# 0134-logic-level-shifter-x8.net
KiCad netlist of a schematic drawn in EAGLE
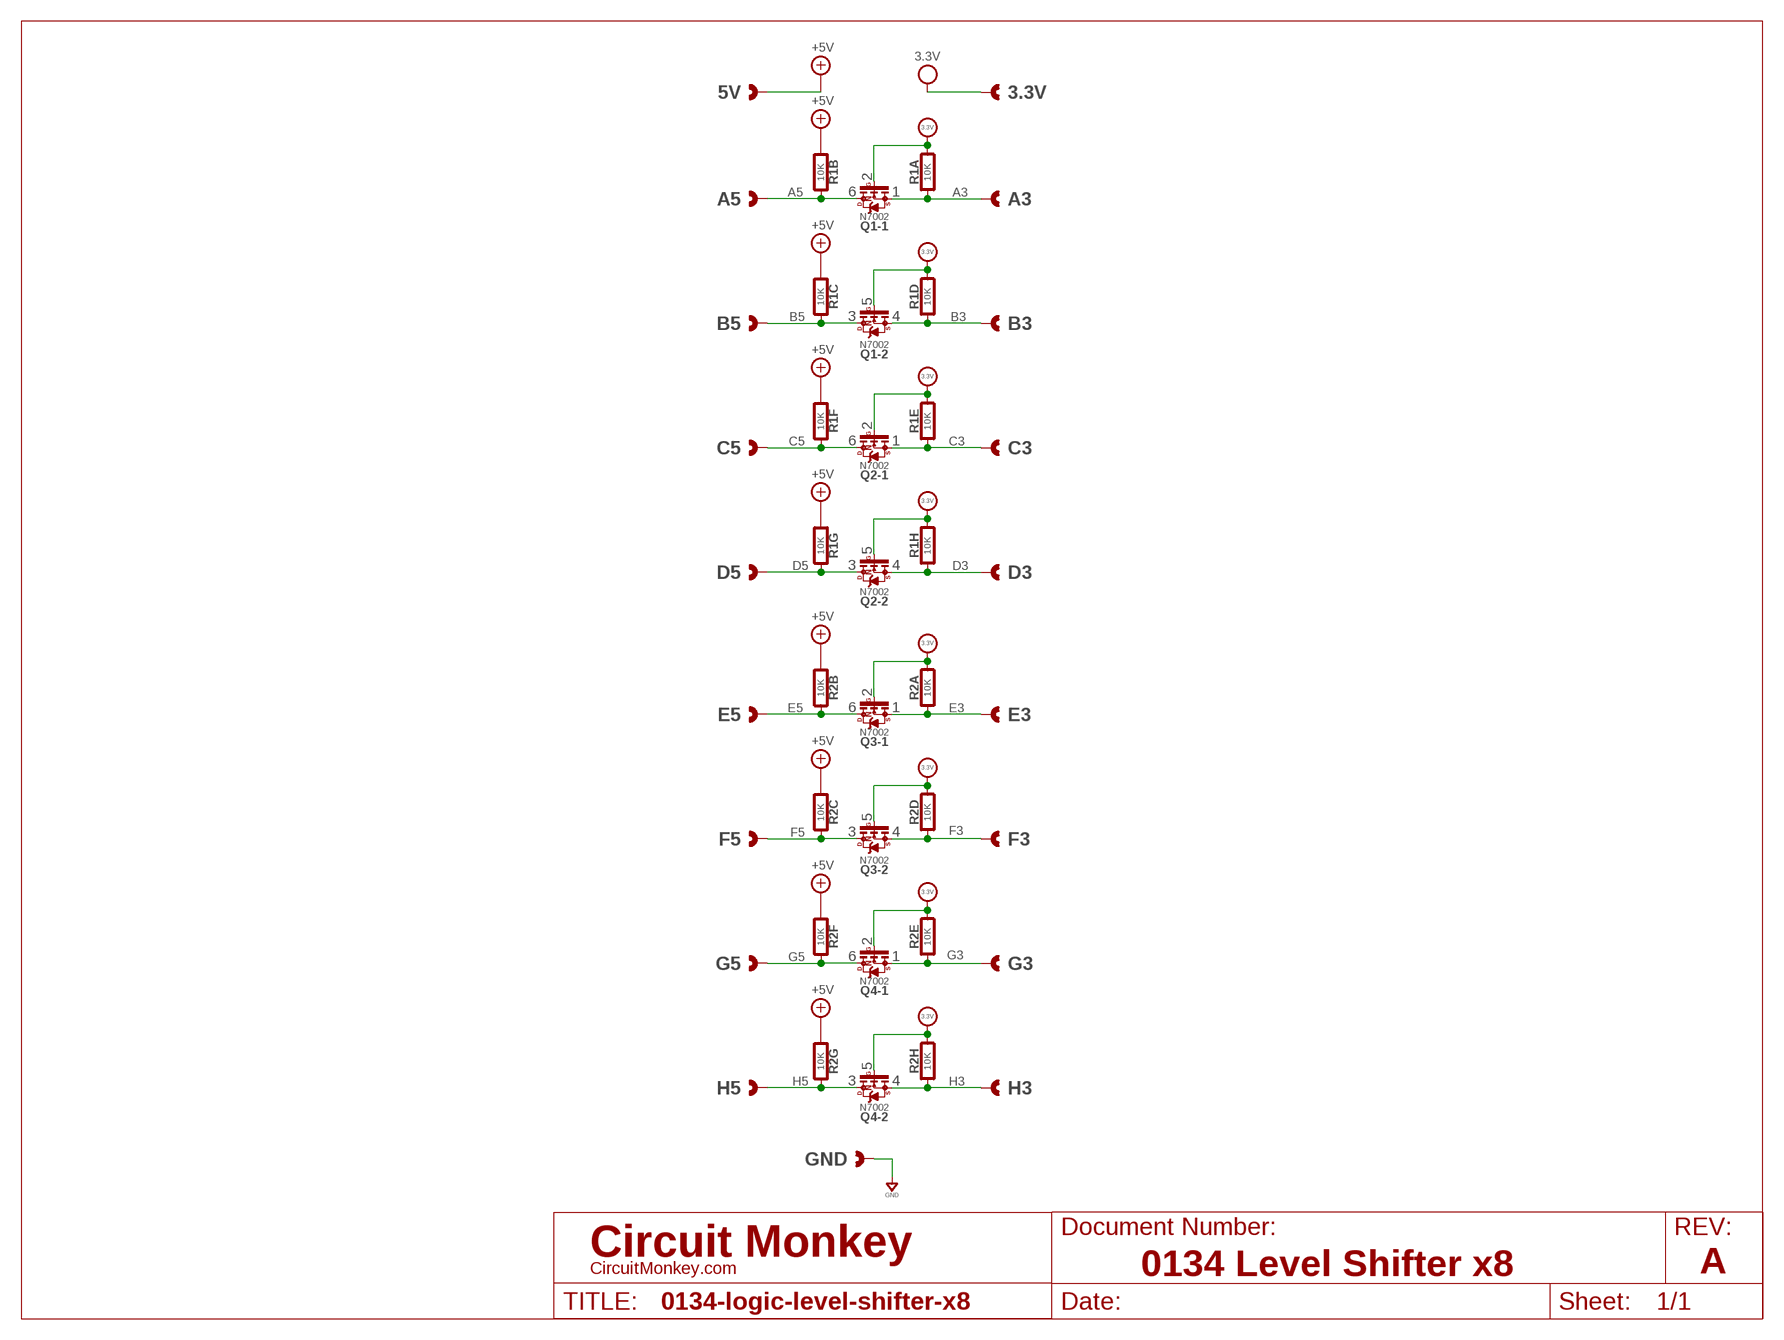
[diagram p0: schematic, sheet 1]

(export (version "E")
  (design (tool "Eeschema 10.0.6"))
  (components
    (comp (ref "3.3V")
      (value "CAST-01X12.00MM")
      (footprint "eagle-import:CAST01-2.00MM")
      (libsource (lib "eagle-import") (part "CAST-01X12.00MM"))
    )
    (comp (ref "5V")
      (value "CAST-01X12.00MM")
      (footprint "eagle-import:CAST01-2.00MM")
      (libsource (lib "eagle-import") (part "CAST-01X12.00MM"))
    )
    (comp (ref "A3")
      (value "CAST-01X12.00MM")
      (footprint "eagle-import:CAST01-2.00MM")
      (libsource (lib "eagle-import") (part "CAST-01X12.00MM"))
    )
    (comp (ref "A5")
      (value "CAST-01X12.00MM")
      (footprint "eagle-import:CAST01-2.00MM")
      (libsource (lib "eagle-import") (part "CAST-01X12.00MM"))
    )
    (comp (ref "B3")
      (value "CAST-01X12.00MM")
      (footprint "eagle-import:CAST01-2.00MM")
      (libsource (lib "eagle-import") (part "CAST-01X12.00MM"))
    )
    (comp (ref "B5")
      (value "CAST-01X12.00MM")
      (footprint "eagle-import:CAST01-2.00MM")
      (libsource (lib "eagle-import") (part "CAST-01X12.00MM"))
    )
    (comp (ref "C3")
      (value "CAST-01X12.00MM")
      (footprint "eagle-import:CAST01-2.00MM")
      (libsource (lib "eagle-import") (part "CAST-01X12.00MM"))
    )
    (comp (ref "C5")
      (value "CAST-01X12.00MM")
      (footprint "eagle-import:CAST01-2.00MM")
      (libsource (lib "eagle-import") (part "CAST-01X12.00MM"))
    )
    (comp (ref "D3")
      (value "CAST-01X12.00MM")
      (footprint "eagle-import:CAST01-2.00MM")
      (libsource (lib "eagle-import") (part "CAST-01X12.00MM"))
    )
    (comp (ref "D5")
      (value "CAST-01X12.00MM")
      (footprint "eagle-import:CAST01-2.00MM")
      (libsource (lib "eagle-import") (part "CAST-01X12.00MM"))
    )
    (comp (ref "E3")
      (value "CAST-01X12.00MM")
      (footprint "eagle-import:CAST01-2.00MM")
      (libsource (lib "eagle-import") (part "CAST-01X12.00MM"))
    )
    (comp (ref "E5")
      (value "CAST-01X12.00MM")
      (footprint "eagle-import:CAST01-2.00MM")
      (libsource (lib "eagle-import") (part "CAST-01X12.00MM"))
    )
    (comp (ref "F3")
      (value "CAST-01X12.00MM")
      (footprint "eagle-import:CAST01-2.00MM")
      (libsource (lib "eagle-import") (part "CAST-01X12.00MM"))
    )
    (comp (ref "F5")
      (value "CAST-01X12.00MM")
      (footprint "eagle-import:CAST01-2.00MM")
      (libsource (lib "eagle-import") (part "CAST-01X12.00MM"))
    )
    (comp (ref "G3")
      (value "CAST-01X12.00MM")
      (footprint "eagle-import:CAST01-2.00MM")
      (libsource (lib "eagle-import") (part "CAST-01X12.00MM"))
    )
    (comp (ref "G5")
      (value "CAST-01X12.00MM")
      (footprint "eagle-import:CAST01-2.00MM")
      (libsource (lib "eagle-import") (part "CAST-01X12.00MM"))
    )
    (comp (ref "GND")
      (value "CAST-01X12.00MM")
      (footprint "eagle-import:CAST01-2.00MM")
      (libsource (lib "eagle-import") (part "CAST-01X12.00MM"))
    )
    (comp (ref "H3")
      (value "CAST-01X12.00MM")
      (footprint "eagle-import:CAST01-2.00MM")
      (libsource (lib "eagle-import") (part "CAST-01X12.00MM"))
    )
    (comp (ref "H5")
      (value "CAST-01X12.00MM")
      (footprint "eagle-import:CAST01-2.00MM")
      (libsource (lib "eagle-import") (part "CAST-01X12.00MM"))
    )
    (comp (ref "Q1")
      (value "N7002")
      (footprint "eagle-import:SOT-563")
      (fields (field (name "MFR") "Toshiba") (field (name "MPN") "SSM6N7002BFE"))
      (libsource (lib "eagle-import") (part "N-FET_DUAL7002"))
    )
    (comp (ref "Q2")
      (value "N7002")
      (footprint "eagle-import:SOT-563")
      (fields (field (name "MFR") "Toshiba") (field (name "MPN") "SSM6N7002BFE"))
      (libsource (lib "eagle-import") (part "N-FET_DUAL7002"))
    )
    (comp (ref "Q3")
      (value "N7002")
      (footprint "eagle-import:SOT-563")
      (fields (field (name "MFR") "Toshiba") (field (name "MPN") "SSM6N7002BFE"))
      (libsource (lib "eagle-import") (part "N-FET_DUAL7002"))
    )
    (comp (ref "Q4")
      (value "N7002")
      (footprint "eagle-import:SOT-563")
      (fields (field (name "MFR") "Toshiba") (field (name "MPN") "SSM6N7002BFE"))
      (libsource (lib "eagle-import") (part "N-FET_DUAL7002"))
    )
    (comp (ref "R1")
      (value "10K")
      (footprint "eagle-import:RESNET_0402_X8")
      (fields (field (name "MFR") "Panasonic") (field (name "MPN") "EXB-2HVxxx"))
      (libsource (lib "eagle-import") (part "RESNET_0402_INDIV_X8PAN"))
    )
    (comp (ref "R2")
      (value "10K")
      (footprint "eagle-import:RESNET_0402_X8")
      (fields (field (name "MFR") "Panasonic") (field (name "MPN") "EXB-2HVxxx"))
      (libsource (lib "eagle-import") (part "RESNET_0402_INDIV_X8PAN"))
    )
  )
  (nets
    (net (code "1") (name "+5V") (class "Default")
      (node (ref "5V") (pin "1") (pinfunction "1_1") (pintype "bidirectional"))
      (node (ref "5V") (pin "P$1") (pinfunction "1_P$1") (pintype "bidirectional"))
      (node (ref "5V") (pin "P$2") (pinfunction "1_P$2") (pintype "bidirectional"))
      (node (ref "R1") (pin "10") (pinfunction "2_10") (pintype "passive"))
      (node (ref "R1") (pin "11") (pinfunction "2_11") (pintype "passive"))
      (node (ref "R1") (pin "14") (pinfunction "2_14") (pintype "passive"))
      (node (ref "R1") (pin "15") (pinfunction "2_15") (pintype "passive"))
      (node (ref "R2") (pin "10") (pinfunction "2_10") (pintype "passive"))
      (node (ref "R2") (pin "11") (pinfunction "2_11") (pintype "passive"))
      (node (ref "R2") (pin "14") (pinfunction "2_14") (pintype "passive"))
      (node (ref "R2") (pin "15") (pinfunction "2_15") (pintype "passive"))
    )
    (net (code "2") (name "/A3") (class "Default")
      (node (ref "A3") (pin "1") (pinfunction "1_1") (pintype "bidirectional"))
      (node (ref "A3") (pin "P$1") (pinfunction "1_P$1") (pintype "bidirectional"))
      (node (ref "A3") (pin "P$2") (pinfunction "1_P$2") (pintype "bidirectional"))
      (node (ref "Q1") (pin "1") (pinfunction "S_1") (pintype "bidirectional"))
      (node (ref "R1") (pin "16") (pinfunction "2_16") (pintype "passive"))
    )
    (net (code "3") (name "/A5") (class "Default")
      (node (ref "A5") (pin "1") (pinfunction "1_1") (pintype "bidirectional"))
      (node (ref "A5") (pin "P$1") (pinfunction "1_P$1") (pintype "bidirectional"))
      (node (ref "A5") (pin "P$2") (pinfunction "1_P$2") (pintype "bidirectional"))
      (node (ref "Q1") (pin "6") (pinfunction "D_6") (pintype "bidirectional"))
      (node (ref "R1") (pin "2") (pinfunction "1_2") (pintype "passive"))
    )
    (net (code "4") (name "/B3") (class "Default")
      (node (ref "B3") (pin "1") (pinfunction "1_1") (pintype "bidirectional"))
      (node (ref "B3") (pin "P$1") (pinfunction "1_P$1") (pintype "bidirectional"))
      (node (ref "B3") (pin "P$2") (pinfunction "1_P$2") (pintype "bidirectional"))
      (node (ref "Q1") (pin "4") (pinfunction "S_4") (pintype "bidirectional"))
      (node (ref "R1") (pin "13") (pinfunction "2_13") (pintype "passive"))
    )
    (net (code "5") (name "/B5") (class "Default")
      (node (ref "B5") (pin "1") (pinfunction "1_1") (pintype "bidirectional"))
      (node (ref "B5") (pin "P$1") (pinfunction "1_P$1") (pintype "bidirectional"))
      (node (ref "B5") (pin "P$2") (pinfunction "1_P$2") (pintype "bidirectional"))
      (node (ref "Q1") (pin "3") (pinfunction "D_3") (pintype "bidirectional"))
      (node (ref "R1") (pin "3") (pinfunction "1_3") (pintype "passive"))
    )
    (net (code "6") (name "/C3") (class "Default")
      (node (ref "C3") (pin "1") (pinfunction "1_1") (pintype "bidirectional"))
      (node (ref "C3") (pin "P$1") (pinfunction "1_P$1") (pintype "bidirectional"))
      (node (ref "C3") (pin "P$2") (pinfunction "1_P$2") (pintype "bidirectional"))
      (node (ref "Q2") (pin "1") (pinfunction "S_1") (pintype "bidirectional"))
      (node (ref "R1") (pin "12") (pinfunction "2_12") (pintype "passive"))
    )
    (net (code "7") (name "/C5") (class "Default")
      (node (ref "C5") (pin "1") (pinfunction "1_1") (pintype "bidirectional"))
      (node (ref "C5") (pin "P$1") (pinfunction "1_P$1") (pintype "bidirectional"))
      (node (ref "C5") (pin "P$2") (pinfunction "1_P$2") (pintype "bidirectional"))
      (node (ref "Q2") (pin "6") (pinfunction "D_6") (pintype "bidirectional"))
      (node (ref "R1") (pin "6") (pinfunction "1_6") (pintype "passive"))
    )
    (net (code "8") (name "/D3") (class "Default")
      (node (ref "D3") (pin "1") (pinfunction "1_1") (pintype "bidirectional"))
      (node (ref "D3") (pin "P$1") (pinfunction "1_P$1") (pintype "bidirectional"))
      (node (ref "D3") (pin "P$2") (pinfunction "1_P$2") (pintype "bidirectional"))
      (node (ref "Q2") (pin "4") (pinfunction "S_4") (pintype "bidirectional"))
      (node (ref "R1") (pin "9") (pinfunction "2_9") (pintype "passive"))
    )
    (net (code "9") (name "/D5") (class "Default")
      (node (ref "D5") (pin "1") (pinfunction "1_1") (pintype "bidirectional"))
      (node (ref "D5") (pin "P$1") (pinfunction "1_P$1") (pintype "bidirectional"))
      (node (ref "D5") (pin "P$2") (pinfunction "1_P$2") (pintype "bidirectional"))
      (node (ref "Q2") (pin "3") (pinfunction "D_3") (pintype "bidirectional"))
      (node (ref "R1") (pin "7") (pinfunction "1_7") (pintype "passive"))
    )
    (net (code "10") (name "/E3") (class "Default")
      (node (ref "E3") (pin "1") (pinfunction "1_1") (pintype "bidirectional"))
      (node (ref "E3") (pin "P$1") (pinfunction "1_P$1") (pintype "bidirectional"))
      (node (ref "E3") (pin "P$2") (pinfunction "1_P$2") (pintype "bidirectional"))
      (node (ref "Q3") (pin "1") (pinfunction "S_1") (pintype "bidirectional"))
      (node (ref "R2") (pin "16") (pinfunction "2_16") (pintype "passive"))
    )
    (net (code "11") (name "/E5") (class "Default")
      (node (ref "E5") (pin "1") (pinfunction "1_1") (pintype "bidirectional"))
      (node (ref "E5") (pin "P$1") (pinfunction "1_P$1") (pintype "bidirectional"))
      (node (ref "E5") (pin "P$2") (pinfunction "1_P$2") (pintype "bidirectional"))
      (node (ref "Q3") (pin "6") (pinfunction "D_6") (pintype "bidirectional"))
      (node (ref "R2") (pin "2") (pinfunction "1_2") (pintype "passive"))
    )
    (net (code "12") (name "/F3") (class "Default")
      (node (ref "F3") (pin "1") (pinfunction "1_1") (pintype "bidirectional"))
      (node (ref "F3") (pin "P$1") (pinfunction "1_P$1") (pintype "bidirectional"))
      (node (ref "F3") (pin "P$2") (pinfunction "1_P$2") (pintype "bidirectional"))
      (node (ref "Q3") (pin "4") (pinfunction "S_4") (pintype "bidirectional"))
      (node (ref "R2") (pin "13") (pinfunction "2_13") (pintype "passive"))
    )
    (net (code "13") (name "/F5") (class "Default")
      (node (ref "F5") (pin "1") (pinfunction "1_1") (pintype "bidirectional"))
      (node (ref "F5") (pin "P$1") (pinfunction "1_P$1") (pintype "bidirectional"))
      (node (ref "F5") (pin "P$2") (pinfunction "1_P$2") (pintype "bidirectional"))
      (node (ref "Q3") (pin "3") (pinfunction "D_3") (pintype "bidirectional"))
      (node (ref "R2") (pin "3") (pinfunction "1_3") (pintype "passive"))
    )
    (net (code "14") (name "/G3") (class "Default")
      (node (ref "G3") (pin "1") (pinfunction "1_1") (pintype "bidirectional"))
      (node (ref "G3") (pin "P$1") (pinfunction "1_P$1") (pintype "bidirectional"))
      (node (ref "G3") (pin "P$2") (pinfunction "1_P$2") (pintype "bidirectional"))
      (node (ref "Q4") (pin "1") (pinfunction "S_1") (pintype "bidirectional"))
      (node (ref "R2") (pin "12") (pinfunction "2_12") (pintype "passive"))
    )
    (net (code "15") (name "/G5") (class "Default")
      (node (ref "G5") (pin "1") (pinfunction "1_1") (pintype "bidirectional"))
      (node (ref "G5") (pin "P$1") (pinfunction "1_P$1") (pintype "bidirectional"))
      (node (ref "G5") (pin "P$2") (pinfunction "1_P$2") (pintype "bidirectional"))
      (node (ref "Q4") (pin "6") (pinfunction "D_6") (pintype "bidirectional"))
      (node (ref "R2") (pin "6") (pinfunction "1_6") (pintype "passive"))
    )
    (net (code "16") (name "/H3") (class "Default")
      (node (ref "H3") (pin "1") (pinfunction "1_1") (pintype "bidirectional"))
      (node (ref "H3") (pin "P$1") (pinfunction "1_P$1") (pintype "bidirectional"))
      (node (ref "H3") (pin "P$2") (pinfunction "1_P$2") (pintype "bidirectional"))
      (node (ref "Q4") (pin "4") (pinfunction "S_4") (pintype "bidirectional"))
      (node (ref "R2") (pin "9") (pinfunction "2_9") (pintype "passive"))
    )
    (net (code "17") (name "/H5") (class "Default")
      (node (ref "H5") (pin "1") (pinfunction "1_1") (pintype "bidirectional"))
      (node (ref "H5") (pin "P$1") (pinfunction "1_P$1") (pintype "bidirectional"))
      (node (ref "H5") (pin "P$2") (pinfunction "1_P$2") (pintype "bidirectional"))
      (node (ref "Q4") (pin "3") (pinfunction "D_3") (pintype "bidirectional"))
      (node (ref "R2") (pin "7") (pinfunction "1_7") (pintype "passive"))
    )
    (net (code "18") (name "3.3V") (class "Default")
      (node (ref "3.3V") (pin "1") (pinfunction "1_1") (pintype "bidirectional"))
      (node (ref "3.3V") (pin "P$1") (pinfunction "1_P$1") (pintype "bidirectional"))
      (node (ref "3.3V") (pin "P$2") (pinfunction "1_P$2") (pintype "bidirectional"))
      (node (ref "Q1") (pin "2") (pinfunction "G_2") (pintype "bidirectional"))
      (node (ref "Q1") (pin "5") (pinfunction "G_5") (pintype "bidirectional"))
      (node (ref "Q2") (pin "2") (pinfunction "G_2") (pintype "bidirectional"))
      (node (ref "Q2") (pin "5") (pinfunction "G_5") (pintype "bidirectional"))
      (node (ref "Q3") (pin "2") (pinfunction "G_2") (pintype "bidirectional"))
      (node (ref "Q3") (pin "5") (pinfunction "G_5") (pintype "bidirectional"))
      (node (ref "Q4") (pin "2") (pinfunction "G_2") (pintype "bidirectional"))
      (node (ref "Q4") (pin "5") (pinfunction "G_5") (pintype "bidirectional"))
      (node (ref "R1") (pin "1") (pinfunction "1_1") (pintype "passive"))
      (node (ref "R1") (pin "4") (pinfunction "1_4") (pintype "passive"))
      (node (ref "R1") (pin "5") (pinfunction "1_5") (pintype "passive"))
      (node (ref "R1") (pin "8") (pinfunction "1_8") (pintype "passive"))
      (node (ref "R2") (pin "1") (pinfunction "1_1") (pintype "passive"))
      (node (ref "R2") (pin "4") (pinfunction "1_4") (pintype "passive"))
      (node (ref "R2") (pin "5") (pinfunction "1_5") (pintype "passive"))
      (node (ref "R2") (pin "8") (pinfunction "1_8") (pintype "passive"))
    )
    (net (code "19") (name "GND") (class "Default")
      (node (ref "GND") (pin "1") (pinfunction "1_1") (pintype "bidirectional"))
      (node (ref "GND") (pin "P$1") (pinfunction "1_P$1") (pintype "bidirectional"))
      (node (ref "GND") (pin "P$2") (pinfunction "1_P$2") (pintype "bidirectional"))
    )
  )
)
